# fullCURRENT_power_logic.net
KiCad netlist of a schematic drawn in Altium Designer
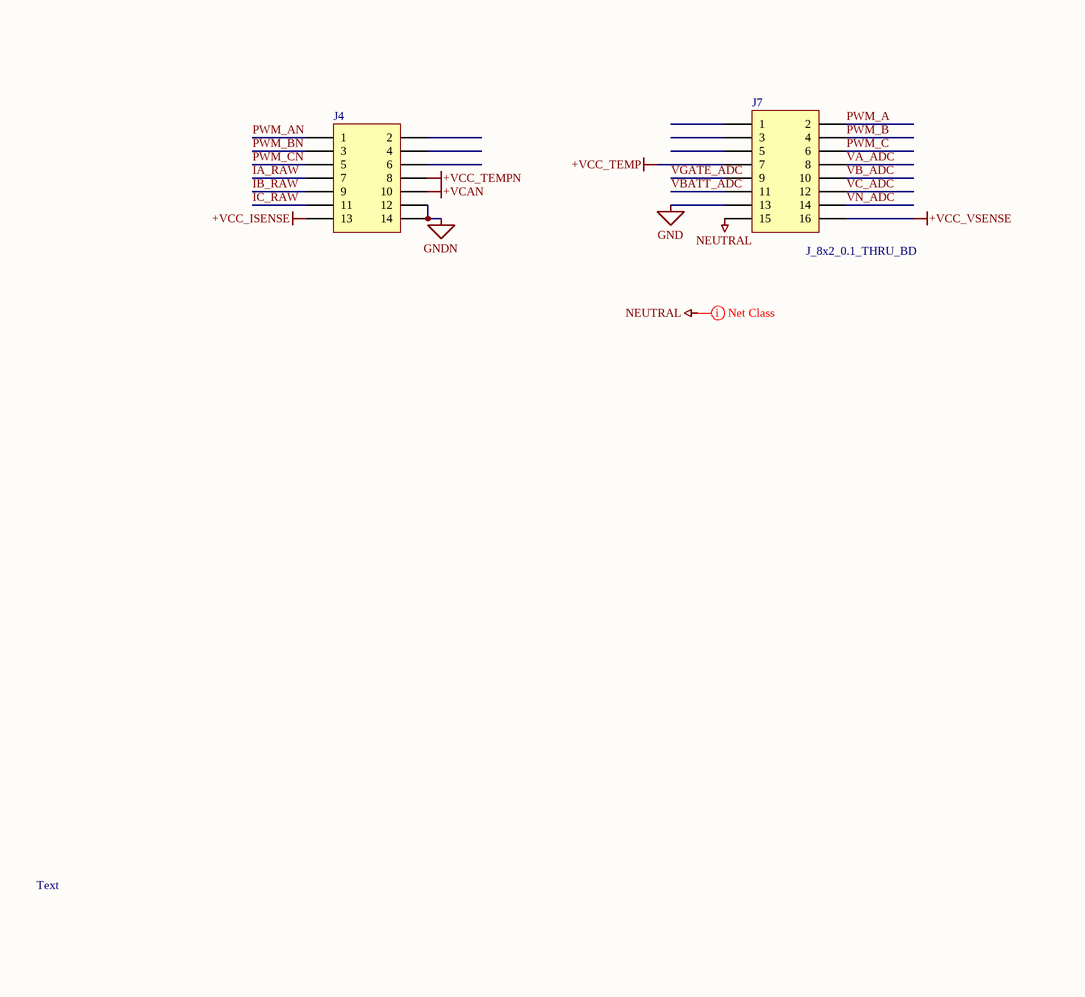
[diagram p0: fullCURRENT power logic.SchDoc, left]
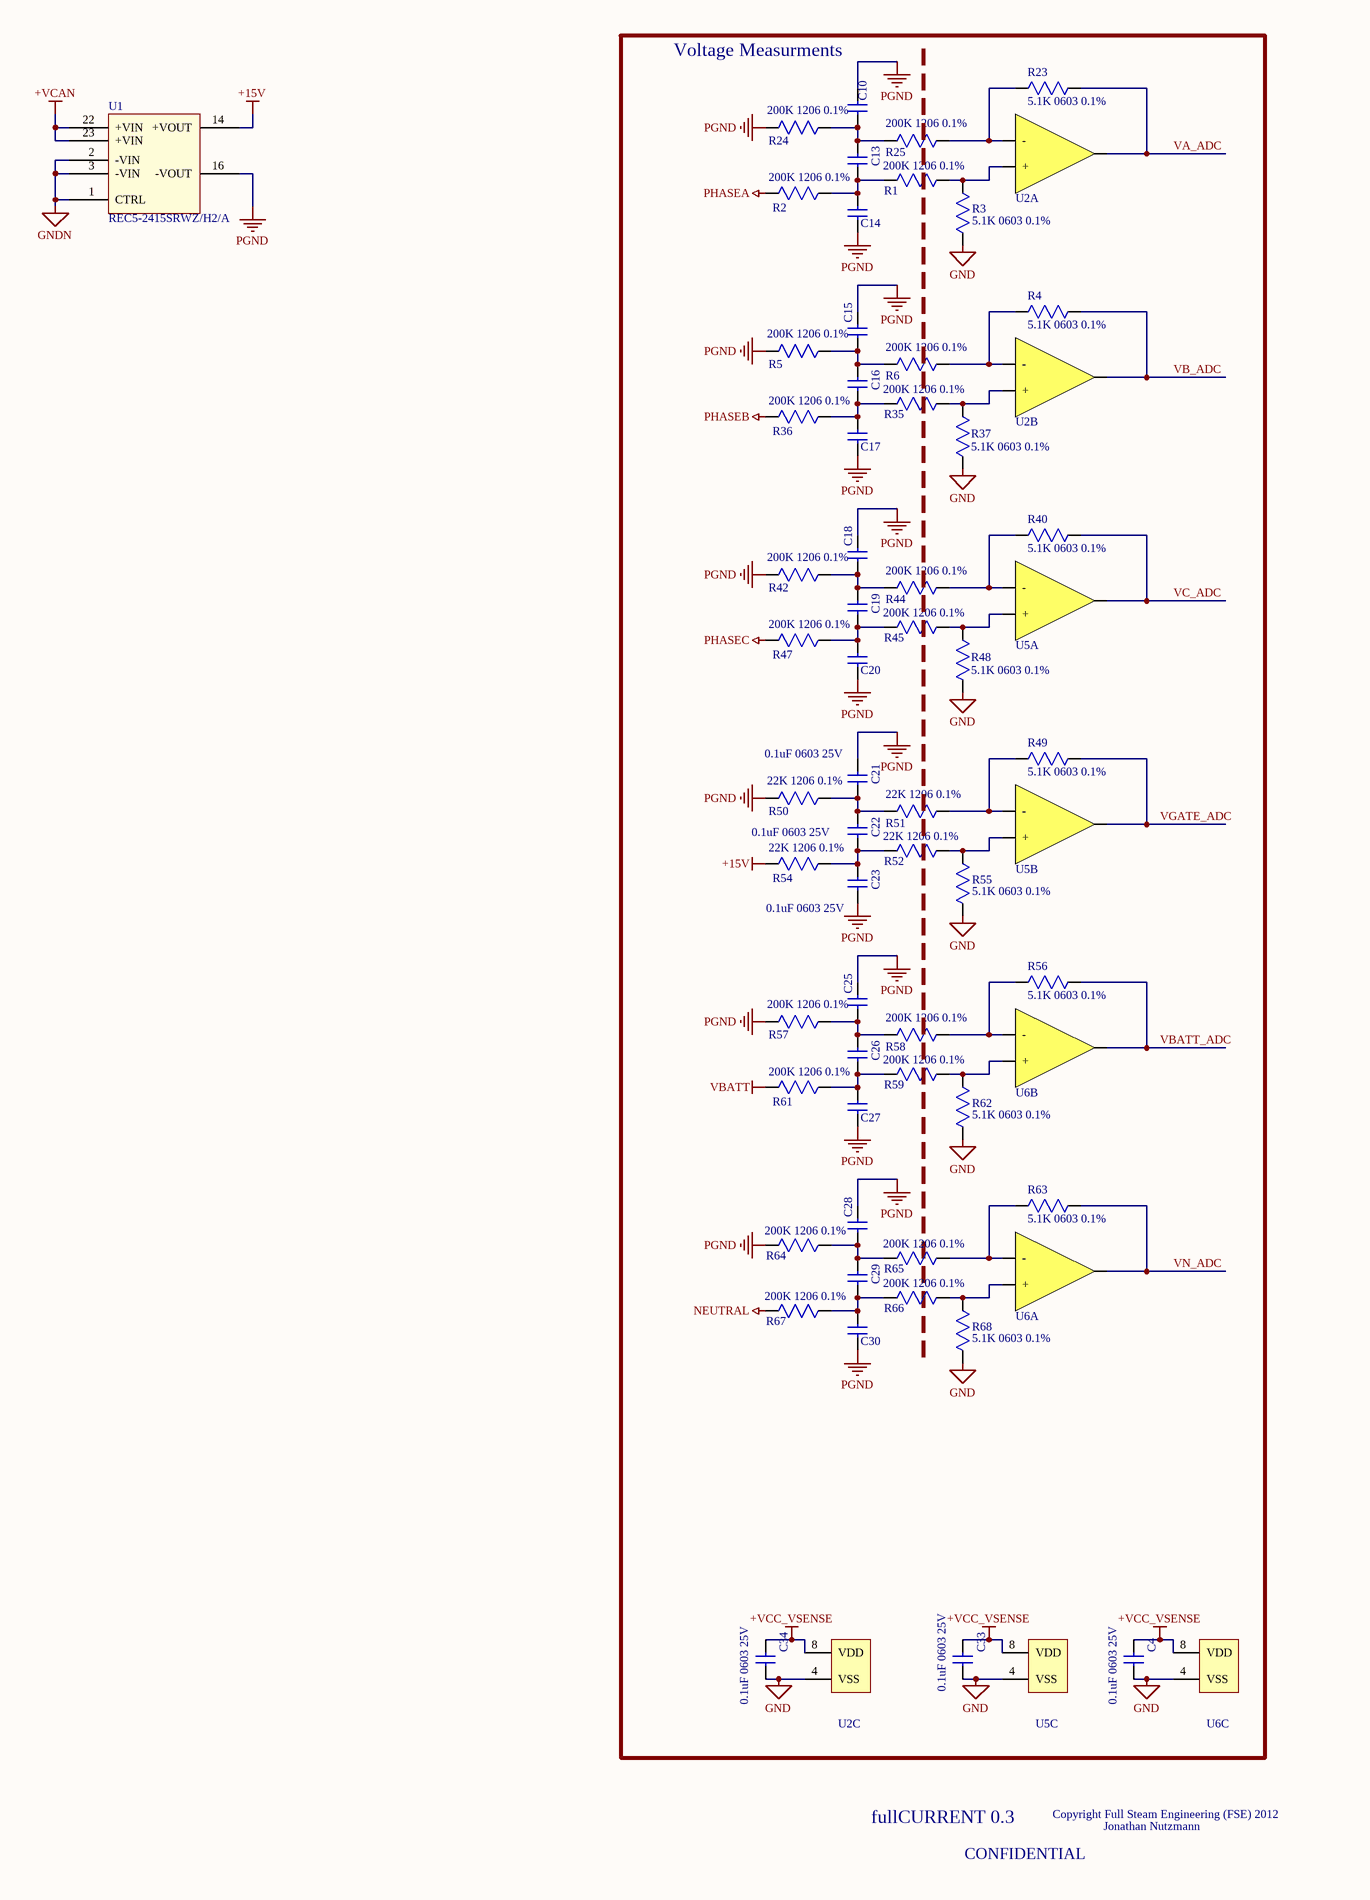
[diagram p1: fullCURRENT power logic.SchDoc, right]

(export (version "E")
  (design (tool "Eeschema 10.0.6"))
  (components
    (comp (ref "C4")
      (value "0.1uF 0603 25V")
      (footprint "0603_cap")
      (description "CAP CERM 0.1uF 0603 X7R")
      (fields (field (name "Comment") "CAP 0603"))
      (libsource (lib "Nutz") (part "C_0603"))
    )
    (comp (ref "C10")
      (value "CAP 0603")
      (footprint "0603_cap")
      (description "CAP CERM 47PF 100V 0603 NP0")
      (libsource (lib "Nutz") (part "C_0603"))
    )
    (comp (ref "C13")
      (value "CAP 0603")
      (footprint "0603_cap")
      (description "CAP CERM 47PF 100V 0603 NP0")
      (libsource (lib "Nutz") (part "C_0603"))
    )
    (comp (ref "C14")
      (value "CAP 0603")
      (footprint "0603_cap")
      (description "CAP CERM 47PF 100V 0603 NP0")
      (libsource (lib "Nutz") (part "C_0603"))
    )
    (comp (ref "C15")
      (value "CAP 0603")
      (footprint "0603_cap")
      (description "CAP CERM 47PF 100V 0603 NP0")
      (libsource (lib "Nutz") (part "C_0603"))
    )
    (comp (ref "C16")
      (value "CAP 0603")
      (footprint "0603_cap")
      (description "CAP CERM 47PF 100V 0603 NP0")
      (libsource (lib "Nutz") (part "C_0603"))
    )
    (comp (ref "C17")
      (value "CAP 0603")
      (footprint "0603_cap")
      (description "CAP CERM 47PF 100V 0603 NP0")
      (libsource (lib "Nutz") (part "C_0603"))
    )
    (comp (ref "C18")
      (value "CAP 0603")
      (footprint "0603_cap")
      (description "CAP CERM 47PF 100V 0603 NP0")
      (libsource (lib "Nutz") (part "C_0603"))
    )
    (comp (ref "C19")
      (value "CAP 0603")
      (footprint "0603_cap")
      (description "CAP CERM 47PF 100V 0603 NP0")
      (libsource (lib "Nutz") (part "C_0603"))
    )
    (comp (ref "C20")
      (value "CAP 0603")
      (footprint "0603_cap")
      (description "CAP CERM 47PF 100V 0603 NP0")
      (libsource (lib "Nutz") (part "C_0603"))
    )
    (comp (ref "C21")
      (value "0.1uF 0603 25V")
      (footprint "0603_cap")
      (description "CAP CERM 0.1uF 0603 X7R")
      (fields (field (name "Comment") "CAP 0603"))
      (libsource (lib "Nutz") (part "C_0603"))
    )
    (comp (ref "C22")
      (value "0.1uF 0603 25V")
      (footprint "0603_cap")
      (description "CAP CERM 0.1uF 0603 X7R")
      (fields (field (name "Comment") "CAP 0603"))
      (libsource (lib "Nutz") (part "C_0603"))
    )
    (comp (ref "C23")
      (value "0.1uF 0603 25V")
      (footprint "0603_cap")
      (description "CAP CERM 0.1uF 0603 X7R")
      (fields (field (name "Comment") "CAP 0603"))
      (libsource (lib "Nutz") (part "C_0603"))
    )
    (comp (ref "C25")
      (value "CAP 0603")
      (footprint "0603_cap")
      (description "CAP CERM 47PF 100V 0603 NP0")
      (libsource (lib "Nutz") (part "C_0603"))
    )
    (comp (ref "C26")
      (value "CAP 0603")
      (footprint "0603_cap")
      (description "CAP CERM 47PF 100V 0603 NP0")
      (libsource (lib "Nutz") (part "C_0603"))
    )
    (comp (ref "C27")
      (value "CAP 0603")
      (footprint "0603_cap")
      (description "CAP CERM 47PF 100V 0603 NP0")
      (libsource (lib "Nutz") (part "C_0603"))
    )
    (comp (ref "C28")
      (value "CAP 0603")
      (footprint "0603_cap")
      (description "CAP CERM 47PF 100V 0603 NP0")
      (libsource (lib "Nutz") (part "C_0603"))
    )
    (comp (ref "C29")
      (value "CAP 0603")
      (footprint "0603_cap")
      (description "CAP CERM 47PF 100V 0603 NP0")
      (libsource (lib "Nutz") (part "C_0603"))
    )
    (comp (ref "C30")
      (value "CAP 0603")
      (footprint "0603_cap")
      (description "CAP CERM 47PF 100V 0603 NP0")
      (libsource (lib "Nutz") (part "C_0603"))
    )
    (comp (ref "C33")
      (value "0.1uF 0603 25V")
      (footprint "0603_cap")
      (description "CAP CERM 0.1uF 0603 X7R")
      (fields (field (name "Comment") "CAP 0603"))
      (libsource (lib "Nutz") (part "C_0603"))
    )
    (comp (ref "C34")
      (value "0.1uF 0603 25V")
      (footprint "0603_cap")
      (description "CAP CERM 0.1uF 0603 X7R")
      (fields (field (name "Comment") "CAP 0603"))
      (libsource (lib "Nutz") (part "C_0603"))
    )
    (comp (ref "J4")
      (value "J_7x2_0.1_THRU_BD")
      (footprint "ZW-07-10-X-D-500-085")
      (description "7 x 2 0.1\" Header")
      (fields
        (field (name "MANUFACTURER PART NUMBER") "ZW-07-19-F-D-1000-085")
        (field (name "MANUFACTURER") "Samtec")
      )
      (libsource (lib "Nutz") (part "J_7x2_0.1_THRU_BD"))
    )
    (comp (ref "J7")
      (value "J_8x2_0.1_THRU_BD")
      (footprint "ZW-08-10-X-D-500-085")
      (description "8 x 2 0.1\" Header")
      (fields
        (field (name "MANUFACTURER PART NUMBER") "ZW-08-10-X-D-500-085")
        (field (name "MANUFACTURER") "Samtec")
      )
      (libsource (lib "Nutz") (part "J_8x2_0.1_THRU_BD"))
    )
    (comp (ref "R1")
      (value "200K 1206 0.1%")
      (footprint "1206_Resistor")
      (description "RES 200K 1206 0.1%")
      (fields (field (name "Comment") "RES 1206"))
      (libsource (lib "Nutz") (part "R_1206"))
    )
    (comp (ref "R2")
      (value "200K 1206 0.1%")
      (footprint "1206_Resistor")
      (description "RES 200K 1206 0.1%")
      (fields (field (name "Comment") "RES 1206"))
      (libsource (lib "Nutz") (part "R_1206"))
    )
    (comp (ref "R3")
      (value "5.1K 0603 0.1%")
      (footprint "0603_res")
      (description "RES 5.1K 0603 0.1%")
      (fields (field (name "Comment") "RES 0603"))
      (libsource (lib "Nutz") (part "R_0603"))
    )
    (comp (ref "R4")
      (value "5.1K 0603 0.1%")
      (footprint "0603_res")
      (description "RES 5.1K 0603 0.1%")
      (fields (field (name "Comment") "RES 0603"))
      (libsource (lib "Nutz") (part "R_0603"))
    )
    (comp (ref "R5")
      (value "200K 1206 0.1%")
      (footprint "1206_Resistor")
      (description "RES 200K 1206 0.1%")
      (fields (field (name "Comment") "RES 1206"))
      (libsource (lib "Nutz") (part "R_1206"))
    )
    (comp (ref "R6")
      (value "200K 1206 0.1%")
      (footprint "1206_Resistor")
      (description "RES 200K 1206 0.1%")
      (fields (field (name "Comment") "RES 1206"))
      (libsource (lib "Nutz") (part "R_1206"))
    )
    (comp (ref "R23")
      (value "5.1K 0603 0.1%")
      (footprint "0603_res")
      (description "RES 5.1K 0603 0.1%")
      (fields (field (name "Comment") "RES 0603"))
      (libsource (lib "Nutz") (part "R_0603"))
    )
    (comp (ref "R24")
      (value "200K 1206 0.1%")
      (footprint "1206_Resistor")
      (description "RES 200K 1206 0.1%")
      (fields (field (name "Comment") "RES 1206"))
      (libsource (lib "Nutz") (part "R_1206"))
    )
    (comp (ref "R25")
      (value "200K 1206 0.1%")
      (footprint "1206_Resistor")
      (description "RES 200K 1206 0.1%")
      (fields (field (name "Comment") "RES 1206"))
      (libsource (lib "Nutz") (part "R_1206"))
    )
    (comp (ref "R35")
      (value "200K 1206 0.1%")
      (footprint "1206_Resistor")
      (description "RES 200K 1206 0.1%")
      (fields (field (name "Comment") "RES 1206"))
      (libsource (lib "Nutz") (part "R_1206"))
    )
    (comp (ref "R36")
      (value "200K 1206 0.1%")
      (footprint "1206_Resistor")
      (description "RES 200K 1206 0.1%")
      (fields (field (name "Comment") "RES 1206"))
      (libsource (lib "Nutz") (part "R_1206"))
    )
    (comp (ref "R37")
      (value "5.1K 0603 0.1%")
      (footprint "0603_res")
      (description "RES 5.1K 0603 0.1%")
      (fields (field (name "Comment") "RES 0603"))
      (libsource (lib "Nutz") (part "R_0603"))
    )
    (comp (ref "R40")
      (value "5.1K 0603 0.1%")
      (footprint "0603_res")
      (description "RES 5.1K 0603 0.1%")
      (fields (field (name "Comment") "RES 0603"))
      (libsource (lib "Nutz") (part "R_0603"))
    )
    (comp (ref "R42")
      (value "200K 1206 0.1%")
      (footprint "1206_Resistor")
      (description "RES 200K 1206 0.1%")
      (fields (field (name "Comment") "RES 1206"))
      (libsource (lib "Nutz") (part "R_1206"))
    )
    (comp (ref "R44")
      (value "200K 1206 0.1%")
      (footprint "1206_Resistor")
      (description "RES 200K 1206 0.1%")
      (fields (field (name "Comment") "RES 1206"))
      (libsource (lib "Nutz") (part "R_1206"))
    )
    (comp (ref "R45")
      (value "200K 1206 0.1%")
      (footprint "1206_Resistor")
      (description "RES 200K 1206 0.1%")
      (fields (field (name "Comment") "RES 1206"))
      (libsource (lib "Nutz") (part "R_1206"))
    )
    (comp (ref "R47")
      (value "200K 1206 0.1%")
      (footprint "1206_Resistor")
      (description "RES 200K 1206 0.1%")
      (fields (field (name "Comment") "RES 1206"))
      (libsource (lib "Nutz") (part "R_1206"))
    )
    (comp (ref "R48")
      (value "5.1K 0603 0.1%")
      (footprint "0603_res")
      (description "RES 5.1K 0603 0.1%")
      (fields (field (name "Comment") "RES 0603"))
      (libsource (lib "Nutz") (part "R_0603"))
    )
    (comp (ref "R49")
      (value "5.1K 0603 0.1%")
      (footprint "0603_res")
      (description "RES 5.1K 0603 0.1%")
      (fields (field (name "Comment") "RES 0603"))
      (libsource (lib "Nutz") (part "R_0603"))
    )
    (comp (ref "R50")
      (value "22K 1206 0.1%")
      (footprint "1206_Resistor")
      (description "RES 22k 1206 0.1%")
      (fields (field (name "Comment") "RES 1206"))
      (libsource (lib "Nutz") (part "R_1206"))
    )
    (comp (ref "R51")
      (value "22K 1206 0.1%")
      (footprint "1206_Resistor")
      (description "RES 22k 1206 0.1%")
      (fields (field (name "Comment") "RES 1206"))
      (libsource (lib "Nutz") (part "R_1206"))
    )
    (comp (ref "R52")
      (value "22K 1206 0.1%")
      (footprint "1206_Resistor")
      (description "RES 22k 1206 0.1%")
      (fields (field (name "Comment") "RES 1206"))
      (libsource (lib "Nutz") (part "R_1206"))
    )
    (comp (ref "R54")
      (value "22K 1206 0.1%")
      (footprint "1206_Resistor")
      (description "RES 22k 1206 0.1%")
      (fields (field (name "Comment") "RES 1206"))
      (libsource (lib "Nutz") (part "R_1206"))
    )
    (comp (ref "R55")
      (value "5.1K 0603 0.1%")
      (footprint "0603_res")
      (description "RES 5.1K 0603 0.1%")
      (fields (field (name "Comment") "RES 0603"))
      (libsource (lib "Nutz") (part "R_0603"))
    )
    (comp (ref "R56")
      (value "5.1K 0603 0.1%")
      (footprint "0603_res")
      (description "RES 5.1K 0603 0.1%")
      (fields (field (name "Comment") "RES 0603"))
      (libsource (lib "Nutz") (part "R_0603"))
    )
    (comp (ref "R57")
      (value "200K 1206 0.1%")
      (footprint "1206_Resistor")
      (description "RES 200K 1206 0.1%")
      (fields (field (name "Comment") "RES 1206"))
      (libsource (lib "Nutz") (part "R_1206"))
    )
    (comp (ref "R58")
      (value "200K 1206 0.1%")
      (footprint "1206_Resistor")
      (description "RES 200K 1206 0.1%")
      (fields (field (name "Comment") "RES 1206"))
      (libsource (lib "Nutz") (part "R_1206"))
    )
    (comp (ref "R59")
      (value "200K 1206 0.1%")
      (footprint "1206_Resistor")
      (description "RES 200K 1206 0.1%")
      (fields (field (name "Comment") "RES 1206"))
      (libsource (lib "Nutz") (part "R_1206"))
    )
    (comp (ref "R61")
      (value "200K 1206 0.1%")
      (footprint "1206_Resistor")
      (description "RES 200K 1206 0.1%")
      (fields (field (name "Comment") "RES 1206"))
      (libsource (lib "Nutz") (part "R_1206"))
    )
    (comp (ref "R62")
      (value "5.1K 0603 0.1%")
      (footprint "0603_res")
      (description "RES 5.1K 0603 0.1%")
      (fields (field (name "Comment") "RES 0603"))
      (libsource (lib "Nutz") (part "R_0603"))
    )
    (comp (ref "R63")
      (value "5.1K 0603 0.1%")
      (footprint "0603_res")
      (description "RES 5.1K 0603 0.1%")
      (fields (field (name "Comment") "RES 0603"))
      (libsource (lib "Nutz") (part "R_0603"))
    )
    (comp (ref "R64")
      (value "200K 1206 0.1%")
      (footprint "1206_Resistor")
      (description "RES 200K 1206 0.1%")
      (fields (field (name "Comment") "RES 1206"))
      (libsource (lib "Nutz") (part "R_1206"))
    )
    (comp (ref "R65")
      (value "200K 1206 0.1%")
      (footprint "1206_Resistor")
      (description "RES 200K 1206 0.1%")
      (fields (field (name "Comment") "RES 1206"))
      (libsource (lib "Nutz") (part "R_1206"))
    )
    (comp (ref "R66")
      (value "200K 1206 0.1%")
      (footprint "1206_Resistor")
      (description "RES 200K 1206 0.1%")
      (fields (field (name "Comment") "RES 1206"))
      (libsource (lib "Nutz") (part "R_1206"))
    )
    (comp (ref "R67")
      (value "200K 1206 0.1%")
      (footprint "1206_Resistor")
      (description "RES 200K 1206 0.1%")
      (fields (field (name "Comment") "RES 1206"))
      (libsource (lib "Nutz") (part "R_1206"))
    )
    (comp (ref "R68")
      (value "5.1K 0603 0.1%")
      (footprint "0603_res")
      (description "RES 5.1K 0603 0.1%")
      (fields (field (name "Comment") "RES 0603"))
      (libsource (lib "Nutz") (part "R_0603"))
    )
    (comp (ref "U1")
      (value "U_REC5-2415SRWZ/H2/A")
      (footprint "REC5-2415SRWZ/H2/A")
      (description "CONV DC/DC 5W 9-36VIN 15VOUT")
      (fields
        (field (name "MANUFACTURER") "Recomb Power")
        (field (name "PART NUMBER") "REC5-2415SRWZ/H2/A")
        (field (name "MANUFACTURER PART NUMBER") "REC5-2415SRWZ/H2/A")
      )
      (libsource (lib "Nutz") (part "U_REC5-2415SRWZ/H2/A"))
    )
    (comp (ref "U2")
      (value "IC OP AMP")
      (footprint "SOIC127P600X175-8N")
      (description "IC OPAMP AUTO-ZERO DUAL 8SOIC")
      (fields (field (name "MANUFACTURER") "Microchip"))
      (libsource (lib "d1_SchLib") (part "U_MCP6V02-E/SN"))
    )
    (comp (ref "U5")
      (value "IC OP AMP")
      (footprint "SOIC127P600X175-8N")
      (description "IC OPAMP AUTO-ZERO DUAL 8SOIC")
      (fields (field (name "MANUFACTURER") "Microchip"))
      (libsource (lib "d1_SchLib") (part "U_MCP6V02-E/SN"))
    )
    (comp (ref "U6")
      (value "IC OP AMP")
      (footprint "SOIC127P600X175-8N")
      (description "IC OPAMP AUTO-ZERO DUAL 8SOIC")
      (fields (field (name "MANUFACTURER") "Microchip"))
      (libsource (lib "d1_SchLib") (part "U_MCP6V02-E/SN"))
    )
  )
  (nets
    (net (code "1") (name "+15V") (class "Default")
      (node (ref "R54") (pin "2") (pinfunction "2_2") (pintype "passive"))
      (node (ref "U1") (pin "14") (pinfunction "+VOUT_14") (pintype "passive"))
    )
    (net (code "2") (name "+VCAN") (class "Default")
      (node (ref "J4") (pin "10") (pinfunction "10_10") (pintype "passive"))
      (node (ref "U1") (pin "22") (pinfunction "+VIN_22") (pintype "passive"))
      (node (ref "U1") (pin "23") (pinfunction "+VIN_23") (pintype "passive"))
    )
    (net (code "3") (name "+VCC_ISENSE") (class "Default")
      (node (ref "J4") (pin "13") (pinfunction "13_13") (pintype "passive"))
    )
    (net (code "4") (name "+VCC_TEMP") (class "Default")
      (node (ref "J7") (pin "7") (pinfunction "7_7") (pintype "passive"))
    )
    (net (code "5") (name "+VCC_TEMPN") (class "Default")
      (node (ref "J4") (pin "8") (pinfunction "8_8") (pintype "passive"))
    )
    (net (code "6") (name "+VCC_VSENSE") (class "Default")
      (node (ref "C33") (pin "2") (pinfunction "2_2") (pintype "passive"))
      (node (ref "C34") (pin "2") (pinfunction "2_2") (pintype "passive"))
      (node (ref "C4") (pin "2") (pinfunction "2_2") (pintype "passive"))
      (node (ref "J7") (pin "16") (pinfunction "16_16") (pintype "passive"))
      (node (ref "U2") (pin "8") (pinfunction "VDD_8") (pintype "passive"))
      (node (ref "U5") (pin "8") (pinfunction "VDD_8") (pintype "passive"))
      (node (ref "U6") (pin "8") (pinfunction "VDD_8") (pintype "passive"))
    )
    (net (code "7") (name "/IA_RAW") (class "Default")
      (node (ref "J4") (pin "7") (pinfunction "7_7") (pintype "passive"))
    )
    (net (code "8") (name "/IB_RAW") (class "Default")
      (node (ref "J4") (pin "9") (pinfunction "9_9") (pintype "passive"))
    )
    (net (code "9") (name "/IC_RAW") (class "Default")
      (node (ref "J4") (pin "11") (pinfunction "11_11") (pintype "passive"))
    )
    (net (code "10") (name "/PWM_A") (class "Default")
      (node (ref "J7") (pin "2") (pinfunction "2_2") (pintype "passive"))
    )
    (net (code "11") (name "/PWM_AN") (class "Default")
      (node (ref "J4") (pin "1") (pinfunction "1_1") (pintype "passive"))
    )
    (net (code "12") (name "/PWM_B") (class "Default")
      (node (ref "J7") (pin "4") (pinfunction "4_4") (pintype "passive"))
    )
    (net (code "13") (name "/PWM_BN") (class "Default")
      (node (ref "J4") (pin "3") (pinfunction "3_3") (pintype "passive"))
    )
    (net (code "14") (name "/PWM_C") (class "Default")
      (node (ref "J7") (pin "6") (pinfunction "6_6") (pintype "passive"))
    )
    (net (code "15") (name "/PWM_CN") (class "Default")
      (node (ref "J4") (pin "5") (pinfunction "5_5") (pintype "passive"))
    )
    (net (code "16") (name "/VA_ADC") (class "Default")
      (node (ref "J7") (pin "8") (pinfunction "8_8") (pintype "passive"))
      (node (ref "R23") (pin "2") (pinfunction "2_2") (pintype "passive"))
      (node (ref "U2") (pin "1") (pinfunction "Vo_1") (pintype "passive"))
    )
    (net (code "17") (name "/VBATT_ADC") (class "Default")
      (node (ref "J7") (pin "11") (pinfunction "11_11") (pintype "passive"))
      (node (ref "R56") (pin "1") (pinfunction "1_1") (pintype "passive"))
      (node (ref "U6") (pin "7") (pinfunction "Vo_7") (pintype "passive"))
    )
    (net (code "18") (name "/VB_ADC") (class "Default")
      (node (ref "J7") (pin "10") (pinfunction "10_10") (pintype "passive"))
      (node (ref "R4") (pin "2") (pinfunction "2_2") (pintype "passive"))
      (node (ref "U2") (pin "7") (pinfunction "Vo_7") (pintype "passive"))
    )
    (net (code "19") (name "/VC_ADC") (class "Default")
      (node (ref "J7") (pin "12") (pinfunction "12_12") (pintype "passive"))
      (node (ref "R40") (pin "1") (pinfunction "1_1") (pintype "passive"))
      (node (ref "U5") (pin "1") (pinfunction "Vo_1") (pintype "passive"))
    )
    (net (code "20") (name "/VGATE_ADC") (class "Default")
      (node (ref "J7") (pin "9") (pinfunction "9_9") (pintype "passive"))
      (node (ref "R49") (pin "1") (pinfunction "1_1") (pintype "passive"))
      (node (ref "U5") (pin "7") (pinfunction "Vo_7") (pintype "passive"))
    )
    (net (code "21") (name "/VN_ADC") (class "Default")
      (node (ref "J7") (pin "14") (pinfunction "14_14") (pintype "passive"))
      (node (ref "R63") (pin "1") (pinfunction "1_1") (pintype "passive"))
      (node (ref "U6") (pin "1") (pinfunction "Vo_1") (pintype "passive"))
    )
    (net (code "22") (name "GND") (class "Default")
      (node (ref "C33") (pin "1") (pinfunction "1_1") (pintype "passive"))
      (node (ref "C34") (pin "1") (pinfunction "1_1") (pintype "passive"))
      (node (ref "C4") (pin "1") (pinfunction "1_1") (pintype "passive"))
      (node (ref "J7") (pin "13") (pinfunction "13_13") (pintype "passive"))
      (node (ref "R3") (pin "1") (pinfunction "1_1") (pintype "passive"))
      (node (ref "R37") (pin "2") (pinfunction "2_2") (pintype "passive"))
      (node (ref "R48") (pin "1") (pinfunction "1_1") (pintype "passive"))
      (node (ref "R55") (pin "1") (pinfunction "1_1") (pintype "passive"))
      (node (ref "R62") (pin "1") (pinfunction "1_1") (pintype "passive"))
      (node (ref "R68") (pin "1") (pinfunction "1_1") (pintype "passive"))
      (node (ref "U2") (pin "4") (pinfunction "VSS_4") (pintype "passive"))
      (node (ref "U5") (pin "4") (pinfunction "VSS_4") (pintype "passive"))
      (node (ref "U6") (pin "4") (pinfunction "VSS_4") (pintype "passive"))
    )
    (net (code "23") (name "GNDN") (class "Default")
      (node (ref "J4") (pin "12") (pinfunction "12_12") (pintype "passive"))
      (node (ref "J4") (pin "14") (pinfunction "14_14") (pintype "passive"))
      (node (ref "U1") (pin "1") (pinfunction "CTRL_1") (pintype "passive"))
      (node (ref "U1") (pin "2") (pinfunction "-VIN_2") (pintype "passive"))
      (node (ref "U1") (pin "3") (pinfunction "-VIN_3") (pintype "passive"))
    )
    (net (code "24") (name "NEUTRAL") (class "Default")
      (node (ref "J7") (pin "15") (pinfunction "15_15") (pintype "passive"))
      (node (ref "R67") (pin "2") (pinfunction "2_2") (pintype "passive"))
    )
    (net (code "25") (name "Net-(C10-Pad1)") (class "Default")
      (node (ref "C10") (pin "1") (pinfunction "1_1") (pintype "passive"))
      (node (ref "C13") (pin "2") (pinfunction "2_2") (pintype "passive"))
      (node (ref "R24") (pin "1") (pinfunction "1_1") (pintype "passive"))
      (node (ref "R25") (pin "2") (pinfunction "2_2") (pintype "passive"))
    )
    (net (code "26") (name "Net-(C13-Pad1)") (class "Default")
      (node (ref "C13") (pin "1") (pinfunction "1_1") (pintype "passive"))
      (node (ref "C14") (pin "2") (pinfunction "2_2") (pintype "passive"))
      (node (ref "R1") (pin "2") (pinfunction "2_2") (pintype "passive"))
      (node (ref "R2") (pin "1") (pinfunction "1_1") (pintype "passive"))
    )
    (net (code "27") (name "Net-(C15-Pad1)") (class "Default")
      (node (ref "C15") (pin "1") (pinfunction "1_1") (pintype "passive"))
      (node (ref "C16") (pin "2") (pinfunction "2_2") (pintype "passive"))
      (node (ref "R5") (pin "1") (pinfunction "1_1") (pintype "passive"))
      (node (ref "R6") (pin "2") (pinfunction "2_2") (pintype "passive"))
    )
    (net (code "28") (name "Net-(C16-Pad1)") (class "Default")
      (node (ref "C16") (pin "1") (pinfunction "1_1") (pintype "passive"))
      (node (ref "C17") (pin "2") (pinfunction "2_2") (pintype "passive"))
      (node (ref "R35") (pin "2") (pinfunction "2_2") (pintype "passive"))
      (node (ref "R36") (pin "1") (pinfunction "1_1") (pintype "passive"))
    )
    (net (code "29") (name "Net-(C18-Pad1)") (class "Default")
      (node (ref "C18") (pin "1") (pinfunction "1_1") (pintype "passive"))
      (node (ref "C19") (pin "2") (pinfunction "2_2") (pintype "passive"))
      (node (ref "R42") (pin "1") (pinfunction "1_1") (pintype "passive"))
      (node (ref "R44") (pin "2") (pinfunction "2_2") (pintype "passive"))
    )
    (net (code "30") (name "Net-(C19-Pad1)") (class "Default")
      (node (ref "C19") (pin "1") (pinfunction "1_1") (pintype "passive"))
      (node (ref "C20") (pin "2") (pinfunction "2_2") (pintype "passive"))
      (node (ref "R45") (pin "2") (pinfunction "2_2") (pintype "passive"))
      (node (ref "R47") (pin "1") (pinfunction "1_1") (pintype "passive"))
    )
    (net (code "31") (name "Net-(C21-Pad1)") (class "Default")
      (node (ref "C21") (pin "1") (pinfunction "1_1") (pintype "passive"))
      (node (ref "C22") (pin "2") (pinfunction "2_2") (pintype "passive"))
      (node (ref "R50") (pin "1") (pinfunction "1_1") (pintype "passive"))
      (node (ref "R51") (pin "2") (pinfunction "2_2") (pintype "passive"))
    )
    (net (code "32") (name "Net-(C22-Pad1)") (class "Default")
      (node (ref "C22") (pin "1") (pinfunction "1_1") (pintype "passive"))
      (node (ref "C23") (pin "2") (pinfunction "2_2") (pintype "passive"))
      (node (ref "R52") (pin "2") (pinfunction "2_2") (pintype "passive"))
      (node (ref "R54") (pin "1") (pinfunction "1_1") (pintype "passive"))
    )
    (net (code "33") (name "Net-(C25-Pad1)") (class "Default")
      (node (ref "C25") (pin "1") (pinfunction "1_1") (pintype "passive"))
      (node (ref "C26") (pin "2") (pinfunction "2_2") (pintype "passive"))
      (node (ref "R57") (pin "1") (pinfunction "1_1") (pintype "passive"))
      (node (ref "R58") (pin "2") (pinfunction "2_2") (pintype "passive"))
    )
    (net (code "34") (name "Net-(C26-Pad1)") (class "Default")
      (node (ref "C26") (pin "1") (pinfunction "1_1") (pintype "passive"))
      (node (ref "C27") (pin "2") (pinfunction "2_2") (pintype "passive"))
      (node (ref "R59") (pin "2") (pinfunction "2_2") (pintype "passive"))
      (node (ref "R61") (pin "1") (pinfunction "1_1") (pintype "passive"))
    )
    (net (code "35") (name "Net-(C28-Pad1)") (class "Default")
      (node (ref "C28") (pin "1") (pinfunction "1_1") (pintype "passive"))
      (node (ref "C29") (pin "2") (pinfunction "2_2") (pintype "passive"))
      (node (ref "R64") (pin "1") (pinfunction "1_1") (pintype "passive"))
      (node (ref "R65") (pin "2") (pinfunction "2_2") (pintype "passive"))
    )
    (net (code "36") (name "Net-(C29-Pad1)") (class "Default")
      (node (ref "C29") (pin "1") (pinfunction "1_1") (pintype "passive"))
      (node (ref "C30") (pin "2") (pinfunction "2_2") (pintype "passive"))
      (node (ref "R66") (pin "2") (pinfunction "2_2") (pintype "passive"))
      (node (ref "R67") (pin "1") (pinfunction "1_1") (pintype "passive"))
    )
    (net (code "37") (name "Net-(U2A-+)") (class "Default")
      (node (ref "R1") (pin "1") (pinfunction "1_1") (pintype "passive"))
      (node (ref "R3") (pin "2") (pinfunction "2_2") (pintype "passive"))
      (node (ref "U2") (pin "3") (pinfunction "+_3") (pintype "passive"))
    )
    (net (code "38") (name "Net-(U2A--)") (class "Default")
      (node (ref "R23") (pin "1") (pinfunction "1_1") (pintype "passive"))
      (node (ref "R25") (pin "1") (pinfunction "1_1") (pintype "passive"))
      (node (ref "U2") (pin "2") (pinfunction "-_2") (pintype "passive"))
    )
    (net (code "39") (name "Net-(U2B-+)") (class "Default")
      (node (ref "R35") (pin "1") (pinfunction "1_1") (pintype "passive"))
      (node (ref "R37") (pin "1") (pinfunction "1_1") (pintype "passive"))
      (node (ref "U2") (pin "5") (pinfunction "+_5") (pintype "passive"))
    )
    (net (code "40") (name "Net-(U2B--)") (class "Default")
      (node (ref "R4") (pin "1") (pinfunction "1_1") (pintype "passive"))
      (node (ref "R6") (pin "1") (pinfunction "1_1") (pintype "passive"))
      (node (ref "U2") (pin "6") (pinfunction "-_6") (pintype "passive"))
    )
    (net (code "41") (name "Net-(U5A-+)") (class "Default")
      (node (ref "R45") (pin "1") (pinfunction "1_1") (pintype "passive"))
      (node (ref "R48") (pin "2") (pinfunction "2_2") (pintype "passive"))
      (node (ref "U5") (pin "3") (pinfunction "+_3") (pintype "passive"))
    )
    (net (code "42") (name "Net-(U5A--)") (class "Default")
      (node (ref "R40") (pin "2") (pinfunction "2_2") (pintype "passive"))
      (node (ref "R44") (pin "1") (pinfunction "1_1") (pintype "passive"))
      (node (ref "U5") (pin "2") (pinfunction "-_2") (pintype "passive"))
    )
    (net (code "43") (name "Net-(U5B-+)") (class "Default")
      (node (ref "R52") (pin "1") (pinfunction "1_1") (pintype "passive"))
      (node (ref "R55") (pin "2") (pinfunction "2_2") (pintype "passive"))
      (node (ref "U5") (pin "5") (pinfunction "+_5") (pintype "passive"))
    )
    (net (code "44") (name "Net-(U5B--)") (class "Default")
      (node (ref "R49") (pin "2") (pinfunction "2_2") (pintype "passive"))
      (node (ref "R51") (pin "1") (pinfunction "1_1") (pintype "passive"))
      (node (ref "U5") (pin "6") (pinfunction "-_6") (pintype "passive"))
    )
    (net (code "45") (name "Net-(U6A-+)") (class "Default")
      (node (ref "R66") (pin "1") (pinfunction "1_1") (pintype "passive"))
      (node (ref "R68") (pin "2") (pinfunction "2_2") (pintype "passive"))
      (node (ref "U6") (pin "3") (pinfunction "+_3") (pintype "passive"))
    )
    (net (code "46") (name "Net-(U6A--)") (class "Default")
      (node (ref "R63") (pin "2") (pinfunction "2_2") (pintype "passive"))
      (node (ref "R65") (pin "1") (pinfunction "1_1") (pintype "passive"))
      (node (ref "U6") (pin "2") (pinfunction "-_2") (pintype "passive"))
    )
    (net (code "47") (name "Net-(U6B-+)") (class "Default")
      (node (ref "R59") (pin "1") (pinfunction "1_1") (pintype "passive"))
      (node (ref "R62") (pin "2") (pinfunction "2_2") (pintype "passive"))
      (node (ref "U6") (pin "5") (pinfunction "+_5") (pintype "passive"))
    )
    (net (code "48") (name "Net-(U6B--)") (class "Default")
      (node (ref "R56") (pin "2") (pinfunction "2_2") (pintype "passive"))
      (node (ref "R58") (pin "1") (pinfunction "1_1") (pintype "passive"))
      (node (ref "U6") (pin "6") (pinfunction "-_6") (pintype "passive"))
    )
    (net (code "49") (name "PGND") (class "Default")
      (node (ref "C10") (pin "2") (pinfunction "2_2") (pintype "passive"))
      (node (ref "C14") (pin "1") (pinfunction "1_1") (pintype "passive"))
      (node (ref "C15") (pin "2") (pinfunction "2_2") (pintype "passive"))
      (node (ref "C17") (pin "1") (pinfunction "1_1") (pintype "passive"))
      (node (ref "C18") (pin "2") (pinfunction "2_2") (pintype "passive"))
      (node (ref "C20") (pin "1") (pinfunction "1_1") (pintype "passive"))
      (node (ref "C21") (pin "2") (pinfunction "2_2") (pintype "passive"))
      (node (ref "C23") (pin "1") (pinfunction "1_1") (pintype "passive"))
      (node (ref "C25") (pin "2") (pinfunction "2_2") (pintype "passive"))
      (node (ref "C27") (pin "1") (pinfunction "1_1") (pintype "passive"))
      (node (ref "C28") (pin "2") (pinfunction "2_2") (pintype "passive"))
      (node (ref "C30") (pin "1") (pinfunction "1_1") (pintype "passive"))
      (node (ref "R24") (pin "2") (pinfunction "2_2") (pintype "passive"))
      (node (ref "R42") (pin "2") (pinfunction "2_2") (pintype "passive"))
      (node (ref "R5") (pin "2") (pinfunction "2_2") (pintype "passive"))
      (node (ref "R50") (pin "2") (pinfunction "2_2") (pintype "passive"))
      (node (ref "R57") (pin "2") (pinfunction "2_2") (pintype "passive"))
      (node (ref "R64") (pin "2") (pinfunction "2_2") (pintype "passive"))
      (node (ref "U1") (pin "16") (pinfunction "-VOUT_16") (pintype "passive"))
    )
    (net (code "50") (name "PHASEA") (class "Default")
      (node (ref "R2") (pin "2") (pinfunction "2_2") (pintype "passive"))
    )
    (net (code "51") (name "PHASEB") (class "Default")
      (node (ref "R36") (pin "2") (pinfunction "2_2") (pintype "passive"))
    )
    (net (code "52") (name "PHASEC") (class "Default")
      (node (ref "R47") (pin "2") (pinfunction "2_2") (pintype "passive"))
    )
    (net (code "53") (name "VBATT") (class "Default")
      (node (ref "R61") (pin "2") (pinfunction "2_2") (pintype "passive"))
    )
    (net (code "54") (name "unconnected-(J4-Pad2)") (class "Default")
      (node (ref "J4") (pin "2") (pinfunction "2_2") (pintype "passive"))
    )
    (net (code "55") (name "unconnected-(J4-Pad4)") (class "Default")
      (node (ref "J4") (pin "4") (pinfunction "4_4") (pintype "passive"))
    )
    (net (code "56") (name "unconnected-(J4-Pad6)") (class "Default")
      (node (ref "J4") (pin "6") (pinfunction "6_6") (pintype "passive"))
    )
    (net (code "57") (name "unconnected-(J7-Pad1)") (class "Default")
      (node (ref "J7") (pin "1") (pinfunction "1_1") (pintype "passive"))
    )
    (net (code "58") (name "unconnected-(J7-Pad3)") (class "Default")
      (node (ref "J7") (pin "3") (pinfunction "3_3") (pintype "passive"))
    )
    (net (code "59") (name "unconnected-(J7-Pad5)") (class "Default")
      (node (ref "J7") (pin "5") (pinfunction "5_5") (pintype "passive"))
    )
  )
)
